# atx_power_control.net
KiCad netlist of a schematic drawn in EAGLE
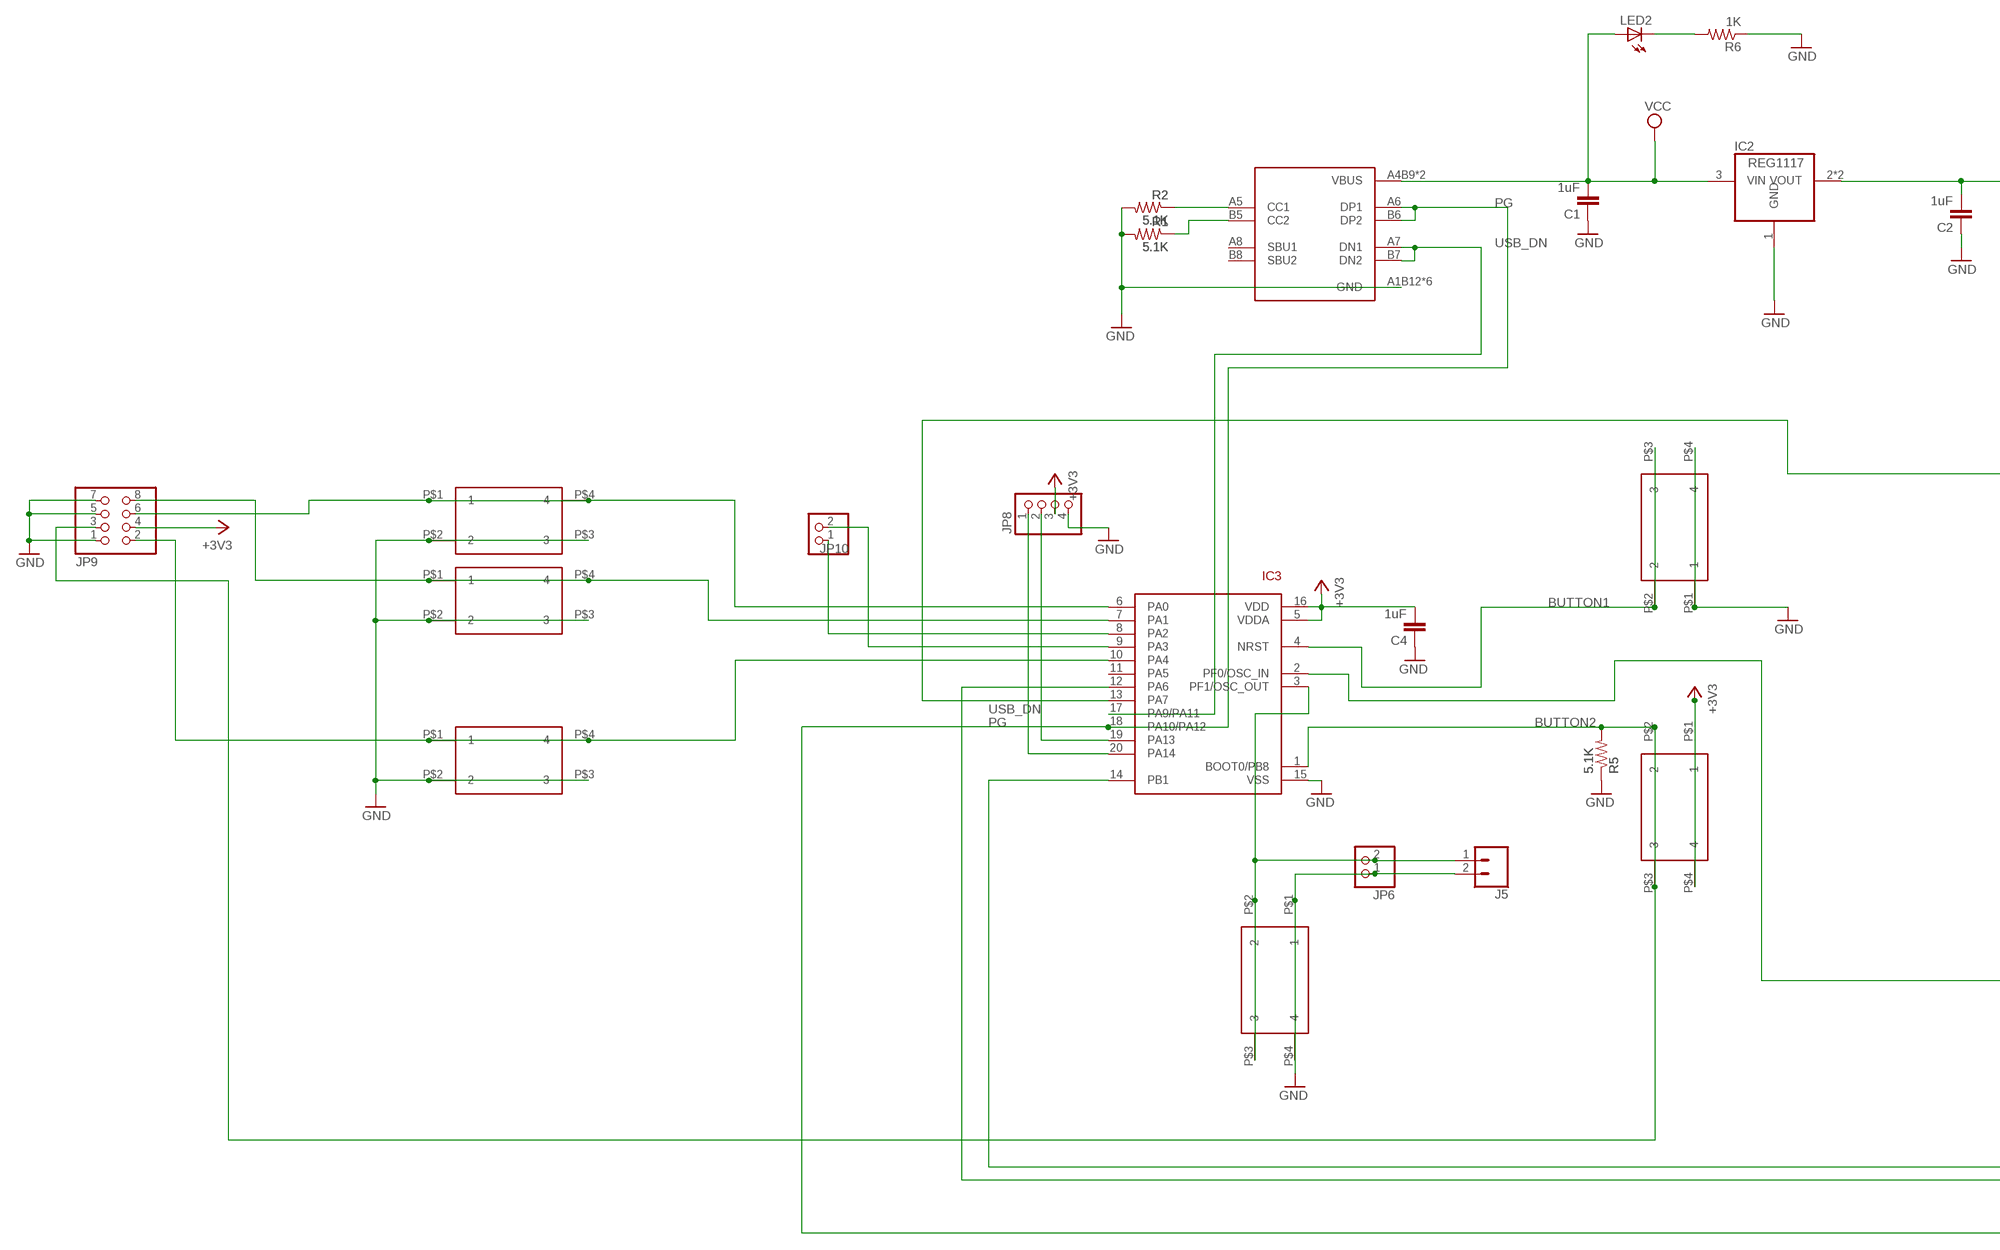
[diagram p0: schematic, sheet 1, part 1 of 2]
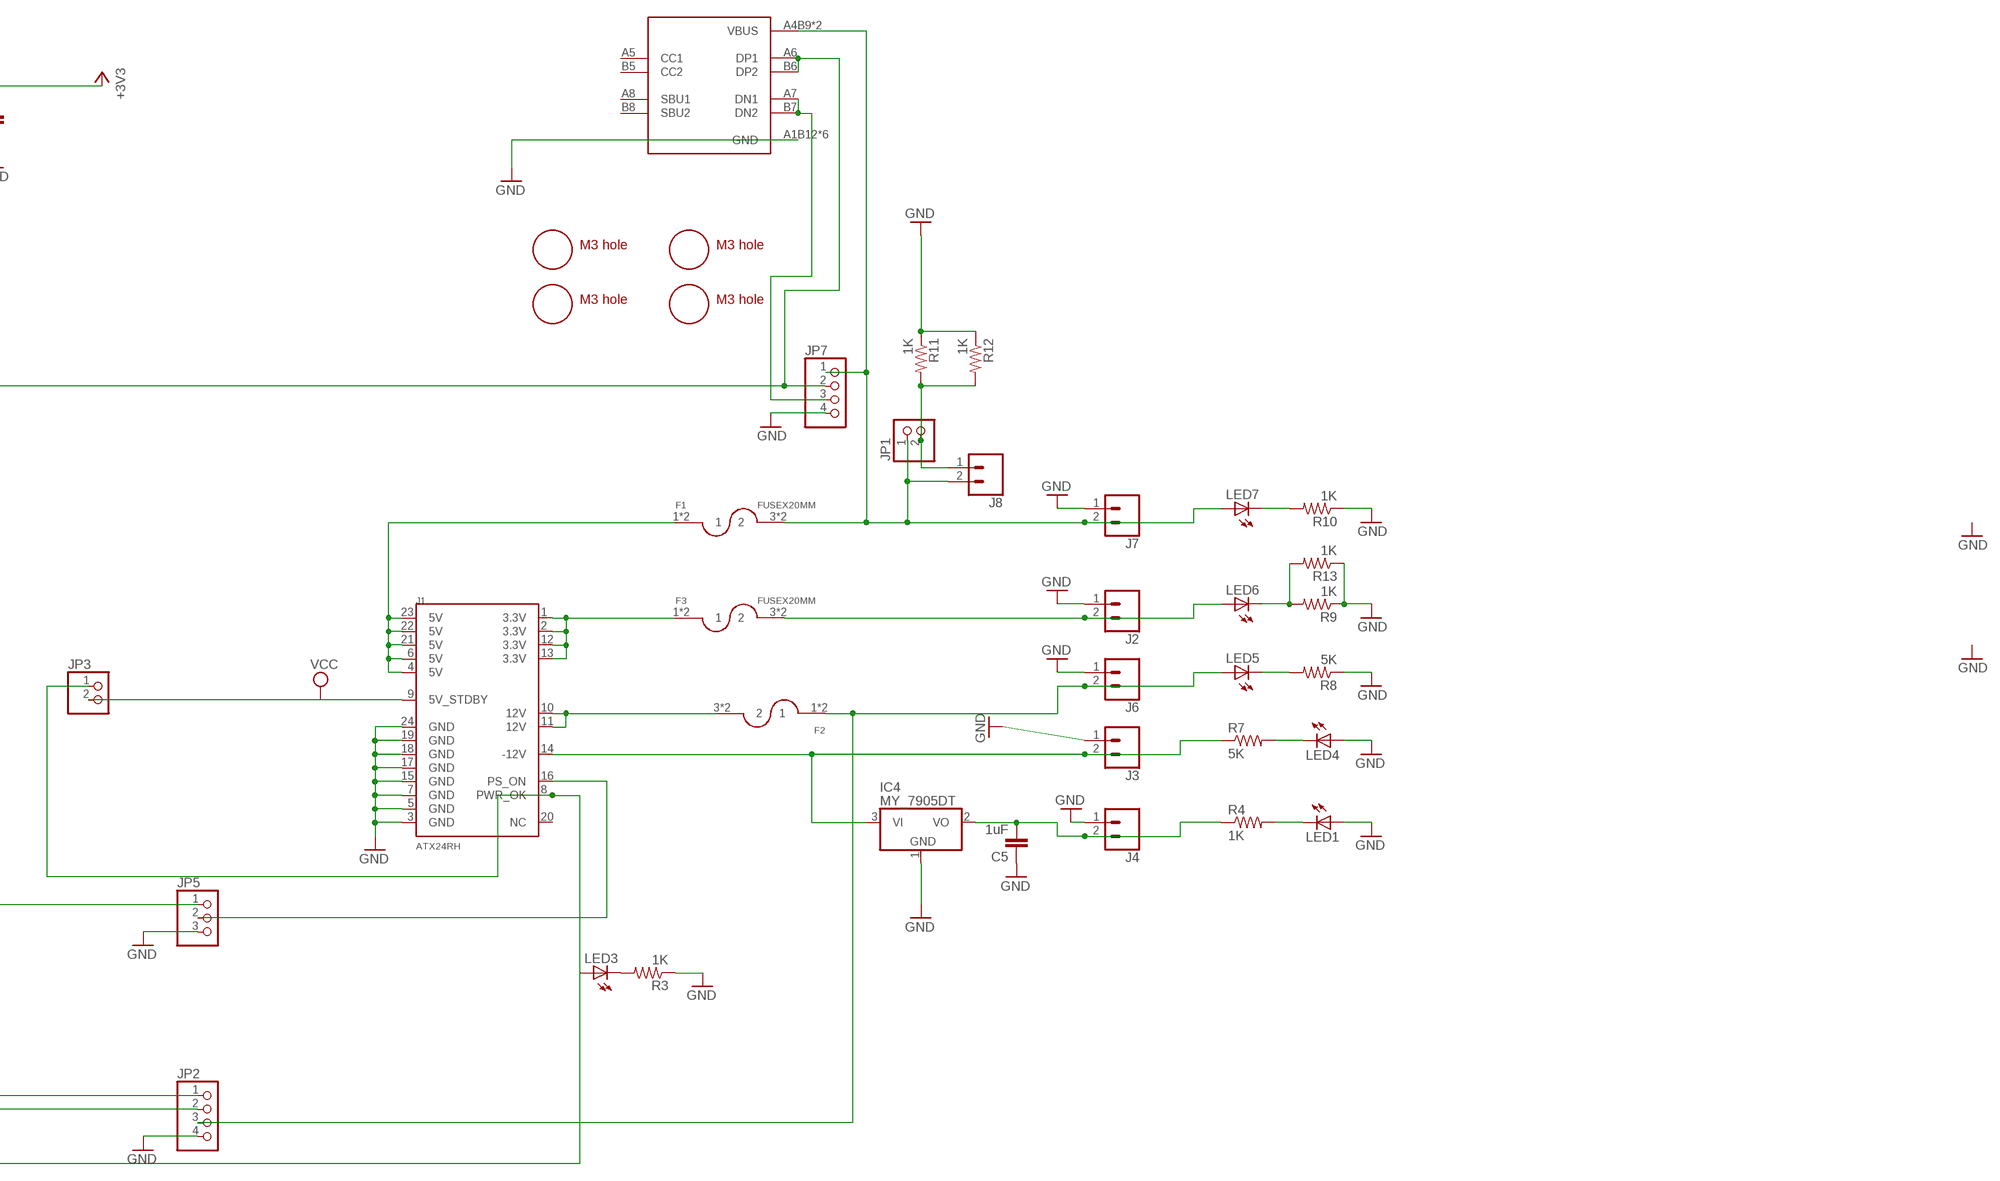
[diagram p1: schematic, sheet 1, part 2 of 2]

(export (version "E")
  (design (tool "Eeschema 10.0.6"))
  (components
    (comp (ref "C1")
      (value "1uF")
      (footprint "eagle-import:0805@1")
      (libsource (lib "eagle-import") (part "CAP0805"))
    )
    (comp (ref "C2")
      (value "1uF")
      (footprint "eagle-import:0805@1")
      (libsource (lib "eagle-import") (part "CAP0805"))
    )
    (comp (ref "C4")
      (value "1uF")
      (footprint "eagle-import:0805@1")
      (libsource (lib "eagle-import") (part "CAP0805"))
    )
    (comp (ref "C5")
      (value "1uF")
      (footprint "eagle-import:0805@1")
      (libsource (lib "eagle-import") (part "CAP0805"))
    )
    (comp (ref "F1")
      (value "FUSEX20MM")
      (footprint "eagle-import:FUSE_5MM")
      (libsource (lib "eagle-import") (part "FUSEX20MM"))
    )
    (comp (ref "F2")
      (value "FUSEX20MM")
      (footprint "eagle-import:FUSE_5MM")
      (libsource (lib "eagle-import") (part "FUSEX20MM"))
    )
    (comp (ref "F3")
      (value "FUSEX20MM")
      (footprint "eagle-import:FUSE_5MM")
      (libsource (lib "eagle-import") (part "FUSEX20MM"))
    )
    (comp (ref "IC2")
      (value "REG1117")
      (footprint "eagle-import:SOT223")
      (libsource (lib "eagle-import") (part "REG1117"))
    )
    (comp (ref "IC3")
      (value "STM32F042F4")
      (footprint "eagle-import:TSSOP20")
      (libsource (lib "eagle-import") (part "STM32F042F4"))
    )
    (comp (ref "IC4")
      (value "MY_7905DT")
      (footprint "eagle-import:ADAFRUIT_TO252")
      (libsource (lib "eagle-import") (part "MY_7905DT"))
    )
    (comp (ref "J1")
      (value "ATX24RH")
      (footprint "eagle-import:ATX24_RIGHT_ANGLE")
      (libsource (lib "eagle-import") (part "ATX24RH"))
    )
    (comp (ref "J2")
      (value "CONN_023.5MM")
      (footprint "eagle-import:SCREWTERMINAL-3.5MM-2")
      (libsource (lib "eagle-import") (part "CONN_023.5MM"))
    )
    (comp (ref "J3")
      (value "CONN_023.5MM")
      (footprint "eagle-import:SCREWTERMINAL-3.5MM-2")
      (libsource (lib "eagle-import") (part "CONN_023.5MM"))
    )
    (comp (ref "J4")
      (value "CONN_023.5MM")
      (footprint "eagle-import:SCREWTERMINAL-3.5MM-2")
      (libsource (lib "eagle-import") (part "CONN_023.5MM"))
    )
    (comp (ref "J5")
      (value "CONN_023.5MM")
      (footprint "eagle-import:SCREWTERMINAL-3.5MM-2")
      (libsource (lib "eagle-import") (part "CONN_023.5MM"))
    )
    (comp (ref "J6")
      (value "CONN_023.5MM")
      (footprint "eagle-import:SCREWTERMINAL-3.5MM-2")
      (libsource (lib "eagle-import") (part "CONN_023.5MM"))
    )
    (comp (ref "J7")
      (value "CONN_023.5MM-NO_SILK")
      (footprint "eagle-import:SCREWTERMINAL-3.5MM-2-NS")
      (libsource (lib "eagle-import") (part "CONN_023.5MM-NO_SILK"))
    )
    (comp (ref "J8")
      (value "CONN_023.5MM")
      (footprint "eagle-import:SCREWTERMINAL-3.5MM-2")
      (libsource (lib "eagle-import") (part "CONN_023.5MM"))
    )
    (comp (ref "JP1")
      (value "PINHD-1X2")
      (footprint "eagle-import:1X02")
      (libsource (lib "eagle-import") (part "PINHD-1X2"))
    )
    (comp (ref "JP2")
      (value "PINHD-1X4")
      (footprint "eagle-import:1X04")
      (libsource (lib "eagle-import") (part "PINHD-1X4"))
    )
    (comp (ref "JP3")
      (value "PINHD-1X2")
      (footprint "eagle-import:1X02")
      (libsource (lib "eagle-import") (part "PINHD-1X2"))
    )
    (comp (ref "JP5")
      (value "PINHD-1X3")
      (footprint "eagle-import:1X03")
      (libsource (lib "eagle-import") (part "PINHD-1X3"))
    )
    (comp (ref "JP6")
      (value "PINHD-1X2")
      (footprint "eagle-import:1X02")
      (libsource (lib "eagle-import") (part "PINHD-1X2"))
    )
    (comp (ref "JP7")
      (value "PINHD-1X4")
      (footprint "eagle-import:1X04")
      (libsource (lib "eagle-import") (part "PINHD-1X4"))
    )
    (comp (ref "JP8")
      (value "PINHD-1X4")
      (footprint "eagle-import:1X04")
      (libsource (lib "eagle-import") (part "PINHD-1X4"))
    )
    (comp (ref "JP9")
      (value "PINHD-2X4")
      (footprint "eagle-import:2X04")
      (libsource (lib "eagle-import") (part "PINHD-2X4"))
    )
    (comp (ref "JP10")
      (value "PINHD-1X2")
      (footprint "eagle-import:1X02")
      (libsource (lib "eagle-import") (part "PINHD-1X2"))
    )
    (comp (ref "LED1")
      (value "LEDCHIP-LED0805")
      (footprint "eagle-import:CHIP-LED0805")
      (libsource (lib "eagle-import") (part "LEDCHIP-LED0805"))
    )
    (comp (ref "LED2")
      (value "LEDCHIP-LED0805")
      (footprint "eagle-import:CHIP-LED0805")
      (libsource (lib "eagle-import") (part "LEDCHIP-LED0805"))
    )
    (comp (ref "LED3")
      (value "LEDCHIP-LED0805")
      (footprint "eagle-import:CHIP-LED0805")
      (libsource (lib "eagle-import") (part "LEDCHIP-LED0805"))
    )
    (comp (ref "LED4")
      (value "LEDCHIP-LED0805")
      (footprint "eagle-import:CHIP-LED0805")
      (libsource (lib "eagle-import") (part "LEDCHIP-LED0805"))
    )
    (comp (ref "LED5")
      (value "LEDCHIP-LED0805")
      (footprint "eagle-import:CHIP-LED0805")
      (libsource (lib "eagle-import") (part "LEDCHIP-LED0805"))
    )
    (comp (ref "LED6")
      (value "LEDCHIP-LED0805")
      (footprint "eagle-import:CHIP-LED0805")
      (libsource (lib "eagle-import") (part "LEDCHIP-LED0805"))
    )
    (comp (ref "LED7")
      (value "LEDCHIP-LED0805")
      (footprint "eagle-import:CHIP-LED0805")
      (libsource (lib "eagle-import") (part "LEDCHIP-LED0805"))
    )
    (comp (ref "R1")
      (value "5.1K")
      (footprint "eagle-import:0805")
      (libsource (lib "eagle-import") (part "joyAnalog_RESISTOR0805-RES"))
    )
    (comp (ref "R2")
      (value "5.1K")
      (footprint "eagle-import:0805")
      (libsource (lib "eagle-import") (part "joyAnalog_RESISTOR0805-RES"))
    )
    (comp (ref "R3")
      (value "1K")
      (footprint "eagle-import:0805")
      (libsource (lib "eagle-import") (part "RESISTOR0805-RES"))
    )
    (comp (ref "R4")
      (value "1K")
      (footprint "eagle-import:0805")
      (libsource (lib "eagle-import") (part "RESISTOR0805-RES"))
    )
    (comp (ref "R5")
      (value "5.1K")
      (footprint "eagle-import:0805")
      (libsource (lib "eagle-import") (part "joyAnalog_RESISTOR0805-RES"))
    )
    (comp (ref "R6")
      (value "1K")
      (footprint "eagle-import:0805")
      (libsource (lib "eagle-import") (part "RESISTOR0805-RES"))
    )
    (comp (ref "R7")
      (value "5K")
      (footprint "eagle-import:0805")
      (libsource (lib "eagle-import") (part "RESISTOR0805-RES"))
    )
    (comp (ref "R8")
      (value "5K")
      (footprint "eagle-import:0805")
      (libsource (lib "eagle-import") (part "RESISTOR0805-RES"))
    )
    (comp (ref "R9")
      (value "1K")
      (footprint "eagle-import:0805")
      (libsource (lib "eagle-import") (part "RESISTOR0805-RES"))
    )
    (comp (ref "R10")
      (value "1K")
      (footprint "eagle-import:0805")
      (libsource (lib "eagle-import") (part "RESISTOR0805-RES"))
    )
    (comp (ref "R11")
      (value "1K")
      (footprint "eagle-import:0805")
      (libsource (lib "eagle-import") (part "RESISTOR0805-RES"))
    )
    (comp (ref "R12")
      (value "1K")
      (footprint "eagle-import:0805")
      (libsource (lib "eagle-import") (part "RESISTOR0805-RES"))
    )
    (comp (ref "R13")
      (value "1K")
      (footprint "eagle-import:0805")
      (libsource (lib "eagle-import") (part "RESISTOR0805-RES"))
    )
    (comp (ref "SW1")
      (value "324_SW")
      (footprint "eagle-import:342_SWICH_FOOT")
      (libsource (lib "eagle-import") (part "324_SW"))
    )
    (comp (ref "SW2")
      (value "324_SW")
      (footprint "eagle-import:342_SWICH_FOOT")
      (libsource (lib "eagle-import") (part "324_SW"))
    )
    (comp (ref "SW3")
      (value "324_SW")
      (footprint "eagle-import:342_SWICH_FOOT")
      (libsource (lib "eagle-import") (part "324_SW"))
    )
    (comp (ref "SW4")
      (value "324_SW")
      (footprint "eagle-import:342_SWICH_FOOT")
      (libsource (lib "eagle-import") (part "324_SW"))
    )
    (comp (ref "SW5")
      (value "324_SW")
      (footprint "eagle-import:342_SWICH_FOOT")
      (libsource (lib "eagle-import") (part "324_SW"))
    )
    (comp (ref "SW7")
      (value "324_SW")
      (footprint "eagle-import:342_SWICH_FOOT")
      (libsource (lib "eagle-import") (part "324_SW"))
    )
    (comp (ref "U$1")
      (value "M3_MOUNTING_HOLE")
      (footprint "eagle-import:M3_MOUNTING_HOLE_PACK")
      (libsource (lib "eagle-import") (part "M3_MOUNTING_HOLE"))
    )
    (comp (ref "U$2")
      (value "M3_MOUNTING_HOLE")
      (footprint "eagle-import:M3_MOUNTING_HOLE_PACK")
      (libsource (lib "eagle-import") (part "M3_MOUNTING_HOLE"))
    )
    (comp (ref "U$3")
      (value "M3_MOUNTING_HOLE")
      (footprint "eagle-import:M3_MOUNTING_HOLE_PACK")
      (libsource (lib "eagle-import") (part "M3_MOUNTING_HOLE"))
    )
    (comp (ref "U$10")
      (value "M3_MOUNTING_HOLE")
      (footprint "eagle-import:M3_MOUNTING_HOLE_PACK")
      (libsource (lib "eagle-import") (part "M3_MOUNTING_HOLE"))
    )
    (comp (ref "U1")
      (value "USBC_16P")
      (footprint "eagle-import:USBC_16P_FOOT")
      (libsource (lib "eagle-import") (part "USBC_16P"))
    )
    (comp (ref "U2")
      (value "USBC_16P")
      (footprint "eagle-import:USBC_16P_FOOT")
      (libsource (lib "eagle-import") (part "USBC_16P"))
    )
  )
  (nets
    (net (code "1") (name "+3V3") (class "Default")
      (node (ref "C2") (pin "2") (pinfunction "2_2") (pintype "passive"))
      (node (ref "C4") (pin "2") (pinfunction "2_2") (pintype "passive"))
      (node (ref "IC2") (pin "2") (pinfunction "VOUT_2") (pintype "output"))
      (node (ref "IC2") (pin "4") (pinfunction "VOUT_4") (pintype "output"))
      (node (ref "IC3") (pin "16") (pinfunction "VDD_16") (pintype "bidirectional"))
      (node (ref "IC3") (pin "5") (pinfunction "VDDA_5") (pintype "bidirectional"))
      (node (ref "JP8") (pin "3") (pinfunction "3_3") (pintype "passive"))
      (node (ref "JP9") (pin "4") (pinfunction "4_4") (pintype "passive"))
      (node (ref "SW4") (pin "P$1") (pinfunction "1_P$1") (pintype "bidirectional"))
      (node (ref "SW4") (pin "P$4") (pinfunction "4_P$4") (pintype "bidirectional"))
    )
    (net (code "2") (name "/BUTTON1") (class "Default")
      (node (ref "IC3") (pin "4") (pinfunction "NRST_4") (pintype "bidirectional"))
      (node (ref "SW3") (pin "P$2") (pinfunction "2_P$2") (pintype "bidirectional"))
      (node (ref "SW3") (pin "P$3") (pinfunction "3_P$3") (pintype "bidirectional"))
    )
    (net (code "3") (name "/BUTTON2") (class "Default")
      (node (ref "IC3") (pin "1") (pinfunction "BOOT0/PB8_1") (pintype "bidirectional"))
      (node (ref "JP9") (pin "3") (pinfunction "3_3") (pintype "passive"))
      (node (ref "R5") (pin "2") (pinfunction "2_2") (pintype "passive"))
      (node (ref "SW4") (pin "P$2") (pinfunction "2_P$2") (pintype "bidirectional"))
      (node (ref "SW4") (pin "P$3") (pinfunction "3_P$3") (pintype "bidirectional"))
    )
    (net (code "4") (name "/PG") (class "Default")
      (node (ref "IC3") (pin "18") (pinfunction "PA10/PA12_18") (pintype "bidirectional"))
      (node (ref "J1") (pin "8") (pinfunction "PWR_OK_8") (pintype "bidirectional"))
      (node (ref "JP3") (pin "1") (pinfunction "1_1") (pintype "passive"))
      (node (ref "LED3") (pin "A") (pinfunction "A_A") (pintype "passive"))
      (node (ref "U2") (pin "A6") (pinfunction "DP1_A6") (pintype "bidirectional"))
      (node (ref "U2") (pin "B6") (pinfunction "DP2_B6") (pintype "bidirectional"))
    )
    (net (code "5") (name "/USB_DN") (class "Default")
      (node (ref "IC3") (pin "17") (pinfunction "PA9/PA11_17") (pintype "bidirectional"))
      (node (ref "U2") (pin "A7") (pinfunction "DN1_A7") (pintype "bidirectional"))
      (node (ref "U2") (pin "B7") (pinfunction "DN2_B7") (pintype "bidirectional"))
    )
    (net (code "6") (name "GND") (class "Default")
      (node (ref "C1") (pin "1") (pinfunction "1_1") (pintype "passive"))
      (node (ref "C2") (pin "1") (pinfunction "1_1") (pintype "passive"))
      (node (ref "C4") (pin "1") (pinfunction "1_1") (pintype "passive"))
      (node (ref "C5") (pin "1") (pinfunction "1_1") (pintype "passive"))
      (node (ref "IC2") (pin "1") (pinfunction "GND_1") (pintype "power_in"))
      (node (ref "IC3") (pin "15") (pinfunction "VSS_15") (pintype "bidirectional"))
      (node (ref "IC4") (pin "1") (pinfunction "GND_1") (pintype "passive"))
      (node (ref "J1") (pin "15") (pinfunction "GND_15") (pintype "bidirectional"))
      (node (ref "J1") (pin "17") (pinfunction "GND_17") (pintype "bidirectional"))
      (node (ref "J1") (pin "18") (pinfunction "GND_18") (pintype "bidirectional"))
      (node (ref "J1") (pin "19") (pinfunction "GND_19") (pintype "bidirectional"))
      (node (ref "J1") (pin "24") (pinfunction "GND_24") (pintype "bidirectional"))
      (node (ref "J1") (pin "3") (pinfunction "GND_3") (pintype "bidirectional"))
      (node (ref "J1") (pin "5") (pinfunction "GND_5") (pintype "bidirectional"))
      (node (ref "J1") (pin "7") (pinfunction "GND_7") (pintype "bidirectional"))
      (node (ref "J2") (pin "1") (pinfunction "1_1") (pintype "passive"))
      (node (ref "J3") (pin "1") (pinfunction "1_1") (pintype "passive"))
      (node (ref "J4") (pin "1") (pinfunction "1_1") (pintype "passive"))
      (node (ref "J5") (pin "2") (pinfunction "2_2") (pintype "passive"))
      (node (ref "J6") (pin "1") (pinfunction "1_1") (pintype "passive"))
      (node (ref "J7") (pin "1") (pinfunction "1_1") (pintype "passive"))
      (node (ref "JP2") (pin "4") (pinfunction "4_4") (pintype "passive"))
      (node (ref "JP5") (pin "3") (pinfunction "3_3") (pintype "passive"))
      (node (ref "JP6") (pin "1") (pinfunction "1_1") (pintype "passive"))
      (node (ref "JP7") (pin "4") (pinfunction "4_4") (pintype "passive"))
      (node (ref "JP8") (pin "4") (pinfunction "4_4") (pintype "passive"))
      (node (ref "JP9") (pin "1") (pinfunction "1_1") (pintype "passive"))
      (node (ref "JP9") (pin "5") (pinfunction "5_5") (pintype "passive"))
      (node (ref "JP9") (pin "7") (pinfunction "7_7") (pintype "passive"))
      (node (ref "LED1") (pin "A") (pinfunction "A_A") (pintype "passive"))
      (node (ref "LED4") (pin "A") (pinfunction "A_A") (pintype "passive"))
      (node (ref "R1") (pin "2") (pinfunction "2_2") (pintype "passive"))
      (node (ref "R10") (pin "1") (pinfunction "1_1") (pintype "passive"))
      (node (ref "R11") (pin "1") (pinfunction "1_1") (pintype "passive"))
      (node (ref "R12") (pin "1") (pinfunction "1_1") (pintype "passive"))
      (node (ref "R13") (pin "1") (pinfunction "1_1") (pintype "passive"))
      (node (ref "R2") (pin "2") (pinfunction "2_2") (pintype "passive"))
      (node (ref "R3") (pin "1") (pinfunction "1_1") (pintype "passive"))
      (node (ref "R5") (pin "1") (pinfunction "1_1") (pintype "passive"))
      (node (ref "R6") (pin "1") (pinfunction "1_1") (pintype "passive"))
      (node (ref "R8") (pin "1") (pinfunction "1_1") (pintype "passive"))
      (node (ref "R9") (pin "1") (pinfunction "1_1") (pintype "passive"))
      (node (ref "SW1") (pin "P$1") (pinfunction "1_P$1") (pintype "bidirectional"))
      (node (ref "SW1") (pin "P$4") (pinfunction "4_P$4") (pintype "bidirectional"))
      (node (ref "SW2") (pin "P$2") (pinfunction "2_P$2") (pintype "bidirectional"))
      (node (ref "SW2") (pin "P$3") (pinfunction "3_P$3") (pintype "bidirectional"))
      (node (ref "SW3") (pin "P$1") (pinfunction "1_P$1") (pintype "bidirectional"))
      (node (ref "SW3") (pin "P$4") (pinfunction "4_P$4") (pintype "bidirectional"))
      (node (ref "SW5") (pin "P$2") (pinfunction "2_P$2") (pintype "bidirectional"))
      (node (ref "SW5") (pin "P$3") (pinfunction "3_P$3") (pintype "bidirectional"))
      (node (ref "SW7") (pin "P$2") (pinfunction "2_P$2") (pintype "bidirectional"))
      (node (ref "SW7") (pin "P$3") (pinfunction "3_P$3") (pintype "bidirectional"))
      (node (ref "U1") (pin "A1B12") (pinfunction "GND_A1B12") (pintype "bidirectional"))
      (node (ref "U1") (pin "B11A12") (pinfunction "GND_B11A12") (pintype "bidirectional"))
      (node (ref "U1") (pin "P$13") (pinfunction "GND_P$13") (pintype "bidirectional"))
      (node (ref "U1") (pin "P$14") (pinfunction "GND_P$14") (pintype "bidirectional"))
      (node (ref "U1") (pin "P$15") (pinfunction "GND_P$15") (pintype "bidirectional"))
      (node (ref "U1") (pin "P$16") (pinfunction "GND_P$16") (pintype "bidirectional"))
      (node (ref "U2") (pin "A1B12") (pinfunction "GND_A1B12") (pintype "bidirectional"))
      (node (ref "U2") (pin "B11A12") (pinfunction "GND_B11A12") (pintype "bidirectional"))
      (node (ref "U2") (pin "P$13") (pinfunction "GND_P$13") (pintype "bidirectional"))
      (node (ref "U2") (pin "P$14") (pinfunction "GND_P$14") (pintype "bidirectional"))
      (node (ref "U2") (pin "P$15") (pinfunction "GND_P$15") (pintype "bidirectional"))
      (node (ref "U2") (pin "P$16") (pinfunction "GND_P$16") (pintype "bidirectional"))
    )
    (net (code "7") (name "Net-(F1-1-Pad2)") (class "Default")
      (node (ref "F1") (pin "1") (pinfunction "1_1") (pintype "bidirectional"))
      (node (ref "F1") (pin "2") (pinfunction "1_2") (pintype "bidirectional"))
      (node (ref "J1") (pin "21") (pinfunction "5V_21") (pintype "bidirectional"))
      (node (ref "J1") (pin "22") (pinfunction "5V_22") (pintype "bidirectional"))
      (node (ref "J1") (pin "23") (pinfunction "5V_23") (pintype "bidirectional"))
      (node (ref "J1") (pin "4") (pinfunction "5V_4") (pintype "bidirectional"))
      (node (ref "J1") (pin "6") (pinfunction "5V_6") (pintype "bidirectional"))
    )
    (net (code "8") (name "Net-(F1-2-Pad3)") (class "Default")
      (node (ref "F1") (pin "3") (pinfunction "2_3") (pintype "bidirectional"))
      (node (ref "F1") (pin "4") (pinfunction "2_4") (pintype "bidirectional"))
      (node (ref "J7") (pin "2") (pinfunction "2_2") (pintype "passive"))
      (node (ref "J8") (pin "2") (pinfunction "2_2") (pintype "passive"))
      (node (ref "JP1") (pin "1") (pinfunction "1_1") (pintype "passive"))
      (node (ref "JP7") (pin "1") (pinfunction "1_1") (pintype "passive"))
      (node (ref "LED7") (pin "A") (pinfunction "A_A") (pintype "passive"))
      (node (ref "U1") (pin "A4B9") (pinfunction "VBUS_A4B9") (pintype "bidirectional"))
      (node (ref "U1") (pin "B4A9") (pinfunction "VBUS_B4A9") (pintype "bidirectional"))
    )
    (net (code "9") (name "Net-(F2-1-Pad2)") (class "Default")
      (node (ref "F2") (pin "1") (pinfunction "1_1") (pintype "bidirectional"))
      (node (ref "F2") (pin "2") (pinfunction "1_2") (pintype "bidirectional"))
      (node (ref "J6") (pin "2") (pinfunction "2_2") (pintype "passive"))
      (node (ref "JP2") (pin "3") (pinfunction "3_3") (pintype "passive"))
      (node (ref "LED5") (pin "A") (pinfunction "A_A") (pintype "passive"))
    )
    (net (code "10") (name "Net-(F2-2-Pad3)") (class "Default")
      (node (ref "F2") (pin "3") (pinfunction "2_3") (pintype "bidirectional"))
      (node (ref "F2") (pin "4") (pinfunction "2_4") (pintype "bidirectional"))
      (node (ref "J1") (pin "10") (pinfunction "12V_10") (pintype "bidirectional"))
      (node (ref "J1") (pin "11") (pinfunction "12V_11") (pintype "bidirectional"))
    )
    (net (code "11") (name "Net-(F3-1-Pad2)") (class "Default")
      (node (ref "F3") (pin "1") (pinfunction "1_1") (pintype "bidirectional"))
      (node (ref "F3") (pin "2") (pinfunction "1_2") (pintype "bidirectional"))
      (node (ref "J1") (pin "1") (pinfunction "3.3V_1") (pintype "bidirectional"))
      (node (ref "J1") (pin "12") (pinfunction "3.3V_12") (pintype "bidirectional"))
      (node (ref "J1") (pin "13") (pinfunction "3.3V_13") (pintype "bidirectional"))
      (node (ref "J1") (pin "2") (pinfunction "3.3V_2") (pintype "bidirectional"))
    )
    (net (code "12") (name "Net-(F3-2-Pad3)") (class "Default")
      (node (ref "F3") (pin "3") (pinfunction "2_3") (pintype "bidirectional"))
      (node (ref "F3") (pin "4") (pinfunction "2_4") (pintype "bidirectional"))
      (node (ref "J2") (pin "2") (pinfunction "2_2") (pintype "passive"))
      (node (ref "LED6") (pin "A") (pinfunction "A_A") (pintype "passive"))
    )
    (net (code "13") (name "Net-(IC3-PA0)") (class "Default")
      (node (ref "IC3") (pin "6") (pinfunction "PA0_6") (pintype "bidirectional"))
      (node (ref "JP9") (pin "6") (pinfunction "6_6") (pintype "passive"))
      (node (ref "SW2") (pin "P$1") (pinfunction "1_P$1") (pintype "bidirectional"))
      (node (ref "SW2") (pin "P$4") (pinfunction "4_P$4") (pintype "bidirectional"))
    )
    (net (code "14") (name "Net-(IC3-PA1)") (class "Default")
      (node (ref "IC3") (pin "7") (pinfunction "PA1_7") (pintype "bidirectional"))
      (node (ref "JP9") (pin "8") (pinfunction "8_8") (pintype "passive"))
      (node (ref "SW5") (pin "P$1") (pinfunction "1_P$1") (pintype "bidirectional"))
      (node (ref "SW5") (pin "P$4") (pinfunction "4_P$4") (pintype "bidirectional"))
    )
    (net (code "15") (name "Net-(IC3-PA2)") (class "Default")
      (node (ref "IC3") (pin "8") (pinfunction "PA2_8") (pintype "bidirectional"))
      (node (ref "JP10") (pin "1") (pinfunction "1_1") (pintype "passive"))
    )
    (net (code "16") (name "Net-(IC3-PA3)") (class "Default")
      (node (ref "IC3") (pin "9") (pinfunction "PA3_9") (pintype "bidirectional"))
      (node (ref "JP10") (pin "2") (pinfunction "2_2") (pintype "passive"))
    )
    (net (code "17") (name "Net-(IC3-PA4)") (class "Default")
      (node (ref "IC3") (pin "10") (pinfunction "PA4_10") (pintype "bidirectional"))
      (node (ref "JP9") (pin "2") (pinfunction "2_2") (pintype "passive"))
      (node (ref "SW7") (pin "P$1") (pinfunction "1_P$1") (pintype "bidirectional"))
      (node (ref "SW7") (pin "P$4") (pinfunction "4_P$4") (pintype "bidirectional"))
    )
    (net (code "18") (name "Net-(IC3-PA6)") (class "Default")
      (node (ref "IC3") (pin "12") (pinfunction "PA6_12") (pintype "bidirectional"))
      (node (ref "JP2") (pin "2") (pinfunction "2_2") (pintype "passive"))
    )
    (net (code "19") (name "Net-(IC3-PA7)") (class "Default")
      (node (ref "IC3") (pin "13") (pinfunction "PA7_13") (pintype "bidirectional"))
      (node (ref "JP7") (pin "2") (pinfunction "2_2") (pintype "passive"))
      (node (ref "U1") (pin "A6") (pinfunction "DP1_A6") (pintype "bidirectional"))
      (node (ref "U1") (pin "B6") (pinfunction "DP2_B6") (pintype "bidirectional"))
    )
    (net (code "20") (name "Net-(IC3-PA13)") (class "Default")
      (node (ref "IC3") (pin "19") (pinfunction "PA13_19") (pintype "bidirectional"))
      (node (ref "JP8") (pin "2") (pinfunction "2_2") (pintype "passive"))
    )
    (net (code "21") (name "Net-(IC3-PA14)") (class "Default")
      (node (ref "IC3") (pin "20") (pinfunction "PA14_20") (pintype "bidirectional"))
      (node (ref "JP8") (pin "1") (pinfunction "1_1") (pintype "passive"))
    )
    (net (code "22") (name "Net-(IC3-PB1)") (class "Default")
      (node (ref "IC3") (pin "14") (pinfunction "PB1_14") (pintype "bidirectional"))
      (node (ref "JP2") (pin "1") (pinfunction "1_1") (pintype "passive"))
    )
    (net (code "23") (name "Net-(IC3-PF0{slash}OSC_IN)") (class "Default")
      (node (ref "IC3") (pin "2") (pinfunction "PF0/OSC_IN_2") (pintype "bidirectional"))
      (node (ref "JP5") (pin "1") (pinfunction "1_1") (pintype "passive"))
    )
    (net (code "24") (name "Net-(IC3-PF1{slash}OSC_OUT)") (class "Default")
      (node (ref "IC3") (pin "3") (pinfunction "PF1/OSC_OUT_3") (pintype "bidirectional"))
      (node (ref "J5") (pin "1") (pinfunction "1_1") (pintype "passive"))
      (node (ref "JP6") (pin "2") (pinfunction "2_2") (pintype "passive"))
      (node (ref "SW1") (pin "P$2") (pinfunction "2_P$2") (pintype "bidirectional"))
      (node (ref "SW1") (pin "P$3") (pinfunction "3_P$3") (pintype "bidirectional"))
    )
    (net (code "25") (name "Net-(IC4-VI)") (class "Default")
      (node (ref "IC4") (pin "3") (pinfunction "VI_3") (pintype "input"))
      (node (ref "J1") (pin "14") (pinfunction "-12V_14") (pintype "bidirectional"))
      (node (ref "J3") (pin "2") (pinfunction "2_2") (pintype "passive"))
      (node (ref "R7") (pin "1") (pinfunction "1_1") (pintype "passive"))
    )
    (net (code "26") (name "Net-(IC4-VO)") (class "Default")
      (node (ref "C5") (pin "2") (pinfunction "2_2") (pintype "passive"))
      (node (ref "IC4") (pin "2") (pinfunction "VO_2") (pintype "passive"))
      (node (ref "J4") (pin "2") (pinfunction "2_2") (pintype "passive"))
      (node (ref "R4") (pin "1") (pinfunction "1_1") (pintype "passive"))
    )
    (net (code "27") (name "Net-(J1-PS_ON)") (class "Default")
      (node (ref "J1") (pin "16") (pinfunction "PS_ON_16") (pintype "bidirectional"))
      (node (ref "JP5") (pin "2") (pinfunction "2_2") (pintype "passive"))
    )
    (net (code "28") (name "Net-(J8-Pad1)") (class "Default")
      (node (ref "J8") (pin "1") (pinfunction "1_1") (pintype "passive"))
      (node (ref "JP1") (pin "2") (pinfunction "2_2") (pintype "passive"))
      (node (ref "R11") (pin "2") (pinfunction "2_2") (pintype "passive"))
      (node (ref "R12") (pin "2") (pinfunction "2_2") (pintype "passive"))
    )
    (net (code "29") (name "Net-(LED1-PadC)") (class "Default")
      (node (ref "LED1") (pin "C") (pinfunction "C_C") (pintype "passive"))
      (node (ref "R4") (pin "2") (pinfunction "2_2") (pintype "passive"))
    )
    (net (code "30") (name "Net-(LED2-PadC)") (class "Default")
      (node (ref "LED2") (pin "C") (pinfunction "C_C") (pintype "passive"))
      (node (ref "R6") (pin "2") (pinfunction "2_2") (pintype "passive"))
    )
    (net (code "31") (name "Net-(LED3-PadC)") (class "Default")
      (node (ref "LED3") (pin "C") (pinfunction "C_C") (pintype "passive"))
      (node (ref "R3") (pin "2") (pinfunction "2_2") (pintype "passive"))
    )
    (net (code "32") (name "Net-(LED4-PadC)") (class "Default")
      (node (ref "LED4") (pin "C") (pinfunction "C_C") (pintype "passive"))
      (node (ref "R7") (pin "2") (pinfunction "2_2") (pintype "passive"))
    )
    (net (code "33") (name "Net-(LED5-PadC)") (class "Default")
      (node (ref "LED5") (pin "C") (pinfunction "C_C") (pintype "passive"))
      (node (ref "R8") (pin "2") (pinfunction "2_2") (pintype "passive"))
    )
    (net (code "34") (name "Net-(LED6-PadC)") (class "Default")
      (node (ref "LED6") (pin "C") (pinfunction "C_C") (pintype "passive"))
      (node (ref "R13") (pin "2") (pinfunction "2_2") (pintype "passive"))
      (node (ref "R9") (pin "2") (pinfunction "2_2") (pintype "passive"))
    )
    (net (code "35") (name "Net-(LED7-PadC)") (class "Default")
      (node (ref "LED7") (pin "C") (pinfunction "C_C") (pintype "passive"))
      (node (ref "R10") (pin "2") (pinfunction "2_2") (pintype "passive"))
    )
    (net (code "36") (name "Net-(U1-DN1)") (class "Default")
      (node (ref "JP7") (pin "3") (pinfunction "3_3") (pintype "passive"))
      (node (ref "U1") (pin "A7") (pinfunction "DN1_A7") (pintype "bidirectional"))
      (node (ref "U1") (pin "B7") (pinfunction "DN2_B7") (pintype "bidirectional"))
    )
    (net (code "37") (name "Net-(U2-CC1)") (class "Default")
      (node (ref "R2") (pin "1") (pinfunction "1_1") (pintype "passive"))
      (node (ref "U2") (pin "A5") (pinfunction "CC1_A5") (pintype "bidirectional"))
    )
    (net (code "38") (name "Net-(U2-CC2)") (class "Default")
      (node (ref "R1") (pin "1") (pinfunction "1_1") (pintype "passive"))
      (node (ref "U2") (pin "B5") (pinfunction "CC2_B5") (pintype "bidirectional"))
    )
    (net (code "39") (name "VCC") (class "Default")
      (node (ref "C1") (pin "2") (pinfunction "2_2") (pintype "passive"))
      (node (ref "IC2") (pin "3") (pinfunction "VIN_3") (pintype "input"))
      (node (ref "J1") (pin "9") (pinfunction "5V_STDBY_9") (pintype "bidirectional"))
      (node (ref "JP3") (pin "2") (pinfunction "2_2") (pintype "passive"))
      (node (ref "LED2") (pin "A") (pinfunction "A_A") (pintype "passive"))
      (node (ref "U2") (pin "A4B9") (pinfunction "VBUS_A4B9") (pintype "bidirectional"))
      (node (ref "U2") (pin "B4A9") (pinfunction "VBUS_B4A9") (pintype "bidirectional"))
    )
    (net (code "40") (name "unconnected-(IC3-PA5-Pad11)") (class "Default")
      (node (ref "IC3") (pin "11") (pinfunction "PA5_11") (pintype "bidirectional"))
    )
    (net (code "41") (name "unconnected-(J1-NC-Pad20)") (class "Default")
      (node (ref "J1") (pin "20") (pinfunction "NC_20") (pintype "bidirectional"))
    )
    (net (code "42") (name "unconnected-(U1-CC1-PadA5)") (class "Default")
      (node (ref "U1") (pin "A5") (pinfunction "CC1_A5") (pintype "bidirectional"))
    )
    (net (code "43") (name "unconnected-(U1-CC2-PadB5)") (class "Default")
      (node (ref "U1") (pin "B5") (pinfunction "CC2_B5") (pintype "bidirectional"))
    )
    (net (code "44") (name "unconnected-(U1-SBU1-PadA8)") (class "Default")
      (node (ref "U1") (pin "A8") (pinfunction "SBU1_A8") (pintype "bidirectional"))
    )
    (net (code "45") (name "unconnected-(U1-SBU2-PadB8)") (class "Default")
      (node (ref "U1") (pin "B8") (pinfunction "SBU2_B8") (pintype "bidirectional"))
    )
    (net (code "46") (name "unconnected-(U2-SBU1-PadA8)") (class "Default")
      (node (ref "U2") (pin "A8") (pinfunction "SBU1_A8") (pintype "bidirectional"))
    )
    (net (code "47") (name "unconnected-(U2-SBU2-PadB8)") (class "Default")
      (node (ref "U2") (pin "B8") (pinfunction "SBU2_B8") (pintype "bidirectional"))
    )
  )
)
